# 08_Amp.net
KiCad netlist of a schematic drawn in Altium Designer
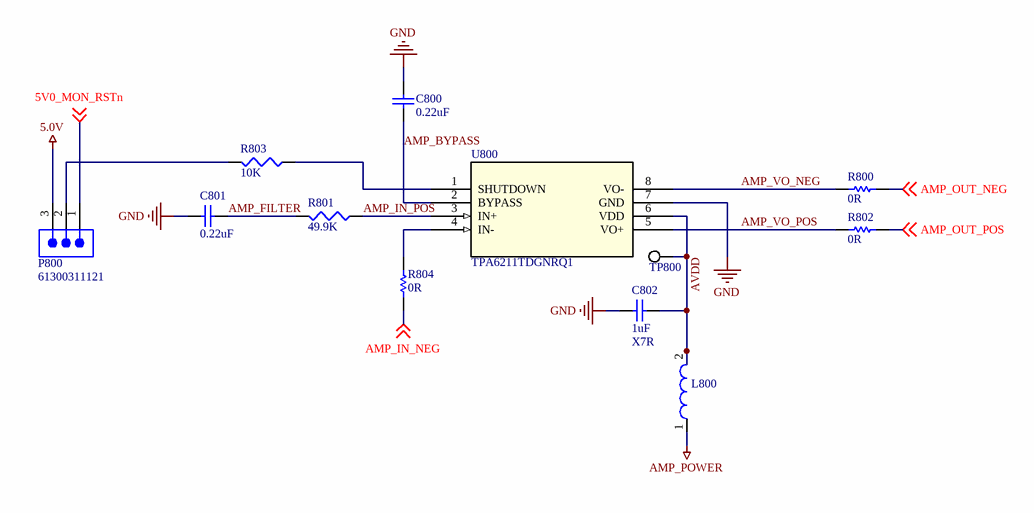
[diagram p0: 08_Amp.SchDoc]

(export (version "E")
  (design (tool "Eeschema 10.0.6"))
  (components
    (comp (ref "C800")
      (value "0.22uF")
      (footprint "CAPC2012M")
      (description "Cap Ceramic 0.22uF 50V X7R 10% SMD 0805 125°C Plastic T/R")
      (fields
        (field (name "MANUFACTURER") "KEMET")
        (field (name "MANUFACTURER PART NUMBER") "C0805C224K5RACAUTO7210")
      )
      (libsource (lib "ECE453") (part "Cap_2"))
    )
    (comp (ref "C801")
      (value "0.22uF")
      (footprint "CAPC2012M")
      (description "Cap Ceramic 0.22uF 50V X7R 10% SMD 0805 125°C Plastic T/R")
      (fields
        (field (name "MANUFACTURER") "KEMET")
        (field (name "MANUFACTURER PART NUMBER") "C0805C224K5RACAUTO7210")
      )
      (libsource (lib "ECE453") (part "Cap_2"))
    )
    (comp (ref "C802")
      (value "1uF")
      (footprint "CAPC2012M")
      (description "CAP CER 1UF 50V X7R 0805")
      (fields
        (field (name "MANUFACTURER") "Samsung")
        (field (name "MANUFACTURER PART NUMBER") "CL21B105KBFNNNE")
        (field (name "DIELECTRIC") "X7R")
      )
      (libsource (lib "ECE453") (part "Cap_5"))
    )
    (comp (ref "L800")
      (value "742792093")
      (footprint "SMD-0805")
      (description "SMD EMI Suppression Ferrite Bead WE-CBF, Z = 2200 Ohm")
      (fields (field (name "MANUFACTURER") "Wurth Electronics") (field (name "TOLERANCE") "25%"))
      (libsource (lib "ECE453") (part "CMP-0220-00169-1"))
    )
    (comp (ref "P800")
      (value "61300311121")
      (footprint "61300311121")
      (libsource (lib "Altium Content Vault") (part "Header_Male_1R_03P"))
    )
    (comp (ref "R800")
      (value "0R")
      (footprint "RESC2013X70X40NL20T20")
      (description "Chip Resistor, 0 Ohm, +/- 1%, 0.125 W, -55 to 155 degC, 0805 (2012 Metric), RoHS, Tape and Reel")
      (fields (field (name "PARTNUMBER") "ERJ-6GEY0R00V") (field (name "TOLERANCE") "5%"))
      (libsource (lib "ECE453") (part "CMP-1665-00002-5"))
    )
    (comp (ref "R801")
      (value "49.9K")
      (footprint "RESC2012M")
      (description "Res Thick Film 0805 49.9K Ohm 1% 0.125W ±100ppm/°C Molded SMD Paper T/R")
      (fields
        (field (name "MANUFACTURER") "Stackpole Electronics")
        (field (name "MANUFACTURER PART NUMBER") "RMCF0805FT49K9")
      )
      (libsource (lib "ECE453") (part "Res3_3"))
    )
    (comp (ref "R802")
      (value "0R")
      (footprint "RESC2013X70X40NL20T20")
      (description "Chip Resistor, 0 Ohm, +/- 1%, 0.125 W, -55 to 155 degC, 0805 (2012 Metric), RoHS, Tape and Reel")
      (fields (field (name "PARTNUMBER") "ERJ-6GEY0R00V") (field (name "TOLERANCE") "5%"))
      (libsource (lib "ECE453") (part "CMP-1665-00002-5"))
    )
    (comp (ref "R803")
      (value "10K")
      (footprint "RESC2012M")
      (description "Res Thick Film 0805 10K Ohm 1% 0.125W ±100ppm/°C Molded SMD Paper T/R")
      (fields
        (field (name "MANUFACTURER") "Stackpole Electronics")
        (field (name "MANUFACTURER PART NUMBER") "RMCF0805FT10K0")
      )
      (libsource (lib "ECE453") (part "Res3"))
    )
    (comp (ref "R804")
      (value "0R")
      (footprint "RESC2013X70X40NL20T20")
      (description "Chip Resistor, 0 Ohm, +/- 1%, 0.125 W, -55 to 155 degC, 0805 (2012 Metric), RoHS, Tape and Reel")
      (fields (field (name "PARTNUMBER") "ERJ-6GEY0R00V") (field (name "TOLERANCE") "5%"))
      (libsource (lib "ECE453") (part "CMP-1665-00002-5"))
    )
    (comp (ref "TP800")
      (value "5019")
      (footprint "KSTN-5019_V")
      (description "Test Point, 1 Position SMD, RoHS, Tape and Reel")
      (libsource (lib "Altium Content Vault") (part "TESTPOINT_WHITE"))
    )
    (comp (ref "U800")
      (value "TPA6211TDGNRQ1")
      (footprint "TPA6211TDGNRQ1-W-THERMALPAD")
      (description "No Description Available")
      (fields (field (name "COPYRIGHT") "Copyright (C) 2023 Ultra Librarian. All rights reserved."))
      (libsource (lib "TPA6211TDGNRQ1") (part "TPA6211TDGNRQ1"))
    )
  )
  (nets
    (net (code "1") (name "/AMP_BYPASS") (class "Default")
      (node (ref "C800") (pin "1") (pinfunction "1_1") (pintype "passive"))
      (node (ref "U800") (pin "2") (pinfunction "BYPASS_2") (pintype "passive"))
    )
    (net (code "2") (name "/AMP_FILTER") (class "Default")
      (node (ref "C801") (pin "1") (pinfunction "1_1") (pintype "passive"))
      (node (ref "R801") (pin "2") (pinfunction "2_2") (pintype "passive"))
    )
    (net (code "3") (name "/AMP_IN_POS") (class "Default")
      (node (ref "R801") (pin "1") (pinfunction "1_1") (pintype "passive"))
      (node (ref "U800") (pin "3") (pinfunction "IN+_3") (pintype "input"))
    )
    (net (code "4") (name "/AMP_VO_NEG") (class "Default")
      (node (ref "R800") (pin "1") (pinfunction "1_1") (pintype "passive"))
      (node (ref "U800") (pin "8") (pinfunction "VO-_8") (pintype "passive"))
    )
    (net (code "5") (name "/AMP_VO_POS") (class "Default")
      (node (ref "R802") (pin "1") (pinfunction "1_1") (pintype "passive"))
      (node (ref "U800") (pin "5") (pinfunction "VO+_5") (pintype "passive"))
    )
    (net (code "6") (name "/AVDD") (class "Default")
      (node (ref "C802") (pin "2") (pinfunction "2_2") (pintype "passive"))
      (node (ref "L800") (pin "2") (pinfunction "2_2") (pintype "passive"))
      (node (ref "TP800") (pin "1") (pinfunction "1_1") (pintype "passive"))
      (node (ref "U800") (pin "6") (pinfunction "VDD_6") (pintype "power_in"))
    )
    (net (code "7") (name "5.0V") (class "Default")
      (node (ref "P800") (pin "3") (pinfunction "3_3") (pintype "passive"))
    )
    (net (code "8") (name "5V0_MON_RSTn") (class "Default")
      (node (ref "P800") (pin "1") (pinfunction "1_1") (pintype "passive"))
    )
    (net (code "9") (name "AMP_IN_NEG") (class "Default")
      (node (ref "R804") (pin "2") (pinfunction "2_2") (pintype "passive"))
    )
    (net (code "10") (name "AMP_OUT_NEG") (class "Default")
      (node (ref "R800") (pin "2") (pinfunction "2_2") (pintype "passive"))
    )
    (net (code "11") (name "AMP_OUT_POS") (class "Default")
      (node (ref "R802") (pin "2") (pinfunction "2_2") (pintype "passive"))
    )
    (net (code "12") (name "AMP_POWER") (class "Default")
      (node (ref "L800") (pin "1") (pinfunction "1_1") (pintype "passive"))
    )
    (net (code "13") (name "GND") (class "Default")
      (node (ref "C800") (pin "2") (pinfunction "2_2") (pintype "passive"))
      (node (ref "C801") (pin "2") (pinfunction "2_2") (pintype "passive"))
      (node (ref "C802") (pin "1") (pinfunction "1_1") (pintype "passive"))
      (node (ref "U800") (pin "7") (pinfunction "GND_7") (pintype "power_in"))
    )
    (net (code "14") (name "Net-(P800-Pad2)") (class "Default")
      (node (ref "P800") (pin "2") (pinfunction "2_2") (pintype "passive"))
      (node (ref "R803") (pin "2") (pinfunction "2_2") (pintype "passive"))
    )
    (net (code "15") (name "Net-(U800-IN-)") (class "Default")
      (node (ref "R804") (pin "1") (pinfunction "1_1") (pintype "passive"))
      (node (ref "U800") (pin "4") (pinfunction "IN-_4") (pintype "input"))
    )
    (net (code "16") (name "Net-(U800-SHUTDOWN)") (class "Default")
      (node (ref "R803") (pin "1") (pinfunction "1_1") (pintype "passive"))
      (node (ref "U800") (pin "1") (pinfunction "SHUTDOWN_1") (pintype "passive"))
    )
  )
)
